# Motor_board_2020_edit.net
KiCad netlist of a schematic drawn in EAGLE
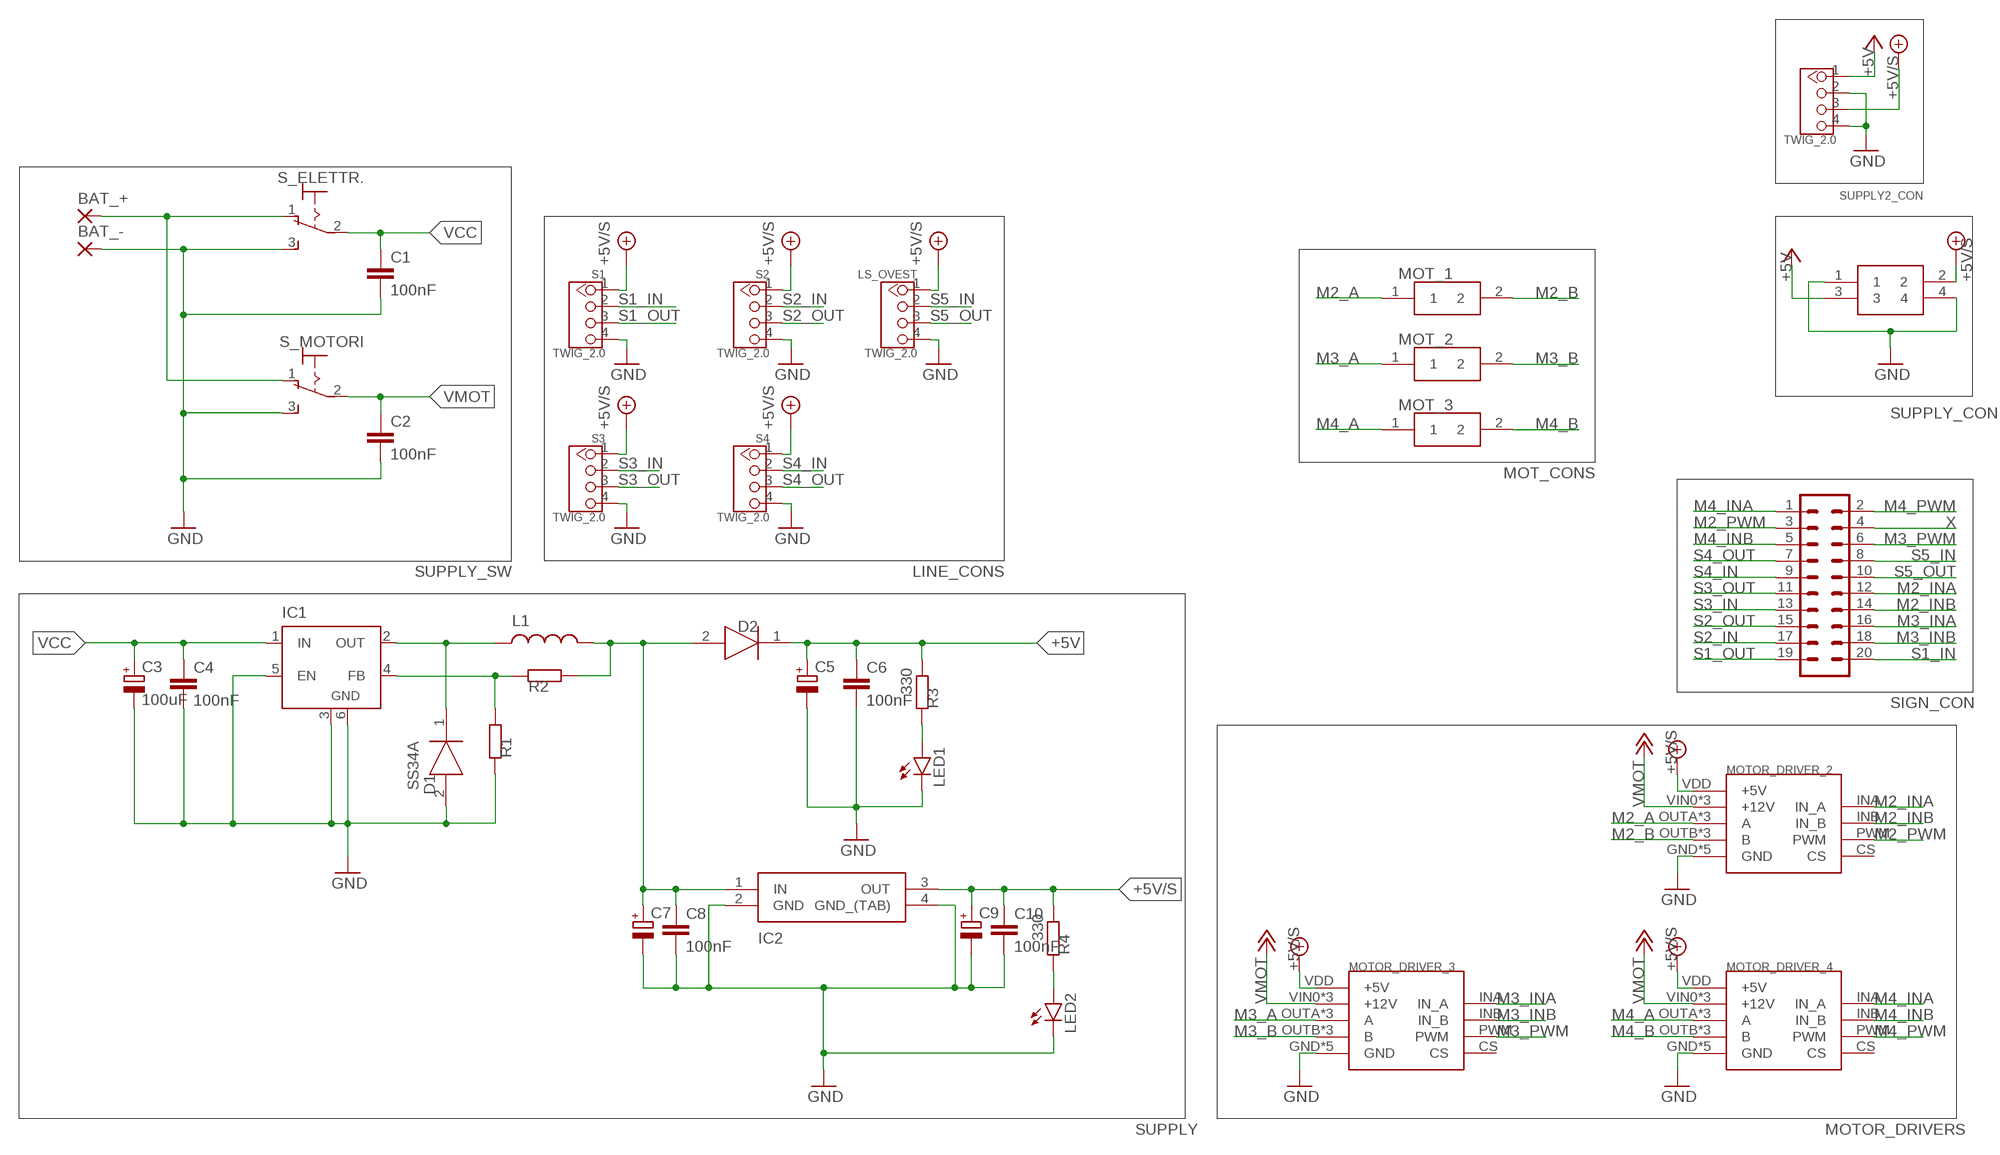
[diagram p0: schematic, sheet 1]

(export (version "E")
  (design (tool "Eeschema 10.0.6"))
  (components
    (comp (ref "BAT_+")
      (value "3,81/1,4")
      (footprint "eagle-import:3,81_1,4")
      (libsource (lib "eagle-import") (part "3,81/1,4"))
    )
    (comp (ref "BAT_-")
      (value "3,81/1,4")
      (footprint "eagle-import:3,81_1,4")
      (libsource (lib "eagle-import") (part "3,81/1,4"))
    )
    (comp (ref "C1")
      (value "100nF")
      (footprint "eagle-import:C1206")
      (libsource (lib "eagle-import") (part "C-EUC1206"))
    )
    (comp (ref "C2")
      (value "100nF")
      (footprint "eagle-import:C1206")
      (libsource (lib "eagle-import") (part "C-EUC1206"))
    )
    (comp (ref "C3")
      (value "100uF")
      (footprint "eagle-import:CT7343")
      (libsource (lib "eagle-import") (part "CPOL-EUCT7343"))
    )
    (comp (ref "C4")
      (value "100nF")
      (footprint "eagle-import:C1206")
      (libsource (lib "eagle-import") (part "C-EUC1206"))
    )
    (comp (ref "C5")
      (value "CPOL-EUE")
      (footprint "eagle-import:PANASONIC_E")
      (libsource (lib "eagle-import") (part "CPOL-EUE"))
    )
    (comp (ref "C6")
      (value "100nF")
      (footprint "eagle-import:C1206")
      (libsource (lib "eagle-import") (part "C-EUC1206"))
    )
    (comp (ref "C7")
      (value "CPOL-EUE")
      (footprint "eagle-import:PANASONIC_E")
      (libsource (lib "eagle-import") (part "CPOL-EUE"))
    )
    (comp (ref "C8")
      (value "100nF")
      (footprint "eagle-import:C1206")
      (libsource (lib "eagle-import") (part "C-EUC1206"))
    )
    (comp (ref "C9")
      (value "CPOL-EUE")
      (footprint "eagle-import:PANASONIC_E")
      (libsource (lib "eagle-import") (part "CPOL-EUE"))
    )
    (comp (ref "C10")
      (value "100nF")
      (footprint "eagle-import:C1206")
      (libsource (lib "eagle-import") (part "C-EUC1206"))
    )
    (comp (ref "D1")
      (value "SS34A")
      (footprint "eagle-import:DIOM5026X262N")
      (fields (field (name "RS_PART_NUMBER") "1711454"))
      (libsource (lib "eagle-import") (part "SS34A"))
    )
    (comp (ref "D2")
      (value "SE20FG-M3_H")
      (footprint "eagle-import:SODFL3718X108N")
      (fields
        (field (name "MANUFACTURER_PART_NUMBER") "SE20FG-M3/H")
        (field (name "RS_PART_NUMBER") "8949262P")
      )
      (libsource (lib "eagle-import") (part "SE20FG-M3_H"))
    )
    (comp (ref "IC1")
      (value "LM2596S")
      (footprint "eagle-import:TO263-5")
      (libsource (lib "eagle-import") (part "LM2596S"))
    )
    (comp (ref "IC2")
      (value "LM2940CS-5.0_NOPB")
      (footprint "eagle-import:TO254P1435X464-4N")
      (fields
        (field (name "MANUFACTURER_PART_NUMBER") "LM2940CS-5.0/NOPB")
        (field (name "MOUSER_PART_NUMBER") "926-LM2940CS-5.0NOPB")
        (field (name "RS_PART_NUMBER") "2508123693")
      )
      (libsource (lib "eagle-import") (part "LM2940CS-5.0_NOPB"))
    )
    (comp (ref "L1")
      (value "47uH")
      (footprint "eagle-import:MSS1260")
      (libsource (lib "eagle-import") (part "MSS1260"))
    )
    (comp (ref "LED1")
      (value "LEDSML1206")
      (footprint "eagle-import:SML1206")
      (libsource (lib "eagle-import") (part "LEDSML1206"))
    )
    (comp (ref "LED2")
      (value "LEDSML1206")
      (footprint "eagle-import:SML1206")
      (libsource (lib "eagle-import") (part "LEDSML1206"))
    )
    (comp (ref "LS_OVEST")
      (value "TWIG_2.0")
      (footprint "eagle-import:2.0_1X4")
      (libsource (lib "eagle-import") (part "TWIG_2.0"))
    )
    (comp (ref "MOTOR_DRIVER_2")
      (value "VNH5019")
      (footprint "eagle-import:VNH5019")
      (libsource (lib "eagle-import") (part "VNH5019"))
    )
    (comp (ref "MOTOR_DRIVER_3")
      (value "VNH5019")
      (footprint "eagle-import:VNH5019")
      (libsource (lib "eagle-import") (part "VNH5019"))
    )
    (comp (ref "MOTOR_DRIVER_4")
      (value "VNH5019")
      (footprint "eagle-import:VNH5019")
      (libsource (lib "eagle-import") (part "VNH5019"))
    )
    (comp (ref "MOT_1")
      (value "43650-0201")
      (footprint "eagle-import:43650-0200")
      (fields (field (name "MOUSER_PART_NUMBER") "538-43650-0201"))
      (libsource (lib "eagle-import") (part "43650-0201"))
    )
    (comp (ref "MOT_2")
      (value "43650-0201")
      (footprint "eagle-import:43650-0200")
      (fields (field (name "MOUSER_PART_NUMBER") "538-43650-0201"))
      (libsource (lib "eagle-import") (part "43650-0201"))
    )
    (comp (ref "MOT_3")
      (value "43650-0201")
      (footprint "eagle-import:43650-0200")
      (fields (field (name "MOUSER_PART_NUMBER") "538-43650-0201"))
      (libsource (lib "eagle-import") (part "43650-0201"))
    )
    (comp (ref "R1")
      (value "330")
      (footprint "eagle-import:R1206")
      (libsource (lib "eagle-import") (part "R-EU_R1206"))
    )
    (comp (ref "R2")
      (value "1,2k")
      (footprint "eagle-import:R1206")
      (libsource (lib "eagle-import") (part "R-EU_R1206"))
    )
    (comp (ref "R3")
      (value "330")
      (footprint "eagle-import:R1206")
      (libsource (lib "eagle-import") (part "R-EU_R1206"))
    )
    (comp (ref "R4")
      (value "330")
      (footprint "eagle-import:R1206")
      (libsource (lib "eagle-import") (part "R-EU_R1206"))
    )
    (comp (ref "S1")
      (value "TWIG_2.0")
      (footprint "eagle-import:2.0_1X4")
      (libsource (lib "eagle-import") (part "TWIG_2.0"))
    )
    (comp (ref "S2")
      (value "TWIG_2.0")
      (footprint "eagle-import:2.0_1X4")
      (libsource (lib "eagle-import") (part "TWIG_2.0"))
    )
    (comp (ref "S3")
      (value "TWIG_2.0")
      (footprint "eagle-import:2.0_1X4")
      (libsource (lib "eagle-import") (part "TWIG_2.0"))
    )
    (comp (ref "S4")
      (value "TWIG_2.0")
      (footprint "eagle-import:2.0_1X4")
      (libsource (lib "eagle-import") (part "TWIG_2.0"))
    )
    (comp (ref "SIGN_CON")
      (value "20V")
      (footprint "eagle-import:20V")
      (libsource (lib "eagle-import") (part "20V"))
    )
    (comp (ref "SUPPLY2_CON")
      (value "TWIG_2.0")
      (footprint "eagle-import:2.0_1X4")
      (libsource (lib "eagle-import") (part "TWIG_2.0"))
    )
    (comp (ref "SUPPLY_CON")
      (value "39-28-1043")
      (footprint "eagle-import:39-28-1043")
      (fields (field (name "MOUSER_PART_NUMBER") "538-39-28-1043") (field (name "RS_PART_NUMBER") "4841899P"))
      (libsource (lib "eagle-import") (part "39-28-1043"))
    )
    (comp (ref "S_ELETTR.")
      (value "320-916")
      (footprint "eagle-import:320-916")
      (libsource (lib "eagle-import") (part "320-916"))
    )
    (comp (ref "S_MOTORI")
      (value "320-916")
      (footprint "eagle-import:320-916")
      (libsource (lib "eagle-import") (part "320-916"))
    )
  )
  (nets
    (net (code "1") (name "+5V") (class "Default")
      (node (ref "C5") (pin "+") (pinfunction "+_+") (pintype "passive"))
      (node (ref "C6") (pin "1") (pinfunction "1_1") (pintype "passive"))
      (node (ref "D2") (pin "1") (pinfunction "K_1") (pintype "bidirectional"))
      (node (ref "R3") (pin "1") (pinfunction "1_1") (pintype "passive"))
      (node (ref "SUPPLY2_CON") (pin "1") (pinfunction "1_1") (pintype "bidirectional"))
      (node (ref "SUPPLY_CON") (pin "3") (pinfunction "3_3") (pintype "bidirectional"))
    )
    (net (code "2") (name "+5V{slash}S") (class "Default")
      (node (ref "C10") (pin "1") (pinfunction "1_1") (pintype "passive"))
      (node (ref "C9") (pin "+") (pinfunction "+_+") (pintype "passive"))
      (node (ref "IC2") (pin "3") (pinfunction "OUT_3") (pintype "output"))
      (node (ref "LS_OVEST") (pin "1") (pinfunction "1_1") (pintype "bidirectional"))
      (node (ref "MOTOR_DRIVER_2") (pin "VDD") (pinfunction "+5V_VDD") (pintype "bidirectional"))
      (node (ref "MOTOR_DRIVER_3") (pin "VDD") (pinfunction "+5V_VDD") (pintype "bidirectional"))
      (node (ref "MOTOR_DRIVER_4") (pin "VDD") (pinfunction "+5V_VDD") (pintype "bidirectional"))
      (node (ref "R4") (pin "1") (pinfunction "1_1") (pintype "passive"))
      (node (ref "S1") (pin "1") (pinfunction "1_1") (pintype "bidirectional"))
      (node (ref "S2") (pin "1") (pinfunction "1_1") (pintype "bidirectional"))
      (node (ref "S3") (pin "1") (pinfunction "1_1") (pintype "bidirectional"))
      (node (ref "S4") (pin "1") (pinfunction "1_1") (pintype "bidirectional"))
      (node (ref "SUPPLY2_CON") (pin "3") (pinfunction "3_3") (pintype "bidirectional"))
      (node (ref "SUPPLY_CON") (pin "2") (pinfunction "2_2") (pintype "bidirectional"))
    )
    (net (code "3") (name "/M2_A") (class "Default")
      (node (ref "MOTOR_DRIVER_2") (pin "OUTA") (pinfunction "A_OUTA") (pintype "bidirectional"))
      (node (ref "MOTOR_DRIVER_2") (pin "OUTA2") (pinfunction "A_OUTA2") (pintype "bidirectional"))
      (node (ref "MOTOR_DRIVER_2") (pin "OUTA3") (pinfunction "A_OUTA3") (pintype "bidirectional"))
      (node (ref "MOT_1") (pin "1") (pinfunction "1_1") (pintype "bidirectional"))
    )
    (net (code "4") (name "/M2_B") (class "Default")
      (node (ref "MOTOR_DRIVER_2") (pin "OUTB") (pinfunction "B_OUTB") (pintype "bidirectional"))
      (node (ref "MOTOR_DRIVER_2") (pin "OUTB1") (pinfunction "B_OUTB1") (pintype "bidirectional"))
      (node (ref "MOTOR_DRIVER_2") (pin "OUTB3") (pinfunction "B_OUTB3") (pintype "bidirectional"))
      (node (ref "MOT_1") (pin "2") (pinfunction "2_2") (pintype "bidirectional"))
    )
    (net (code "5") (name "/M2_INA") (class "Default")
      (node (ref "MOTOR_DRIVER_2") (pin "INA") (pinfunction "IN_A_INA") (pintype "bidirectional"))
      (node (ref "SIGN_CON") (pin "12") (pinfunction "12_12") (pintype "passive"))
    )
    (net (code "6") (name "/M2_INB") (class "Default")
      (node (ref "MOTOR_DRIVER_2") (pin "INB") (pinfunction "IN_B_INB") (pintype "bidirectional"))
      (node (ref "SIGN_CON") (pin "14") (pinfunction "14_14") (pintype "passive"))
    )
    (net (code "7") (name "/M2_PWM") (class "Default")
      (node (ref "MOTOR_DRIVER_2") (pin "PWM") (pinfunction "PWM_PWM") (pintype "bidirectional"))
      (node (ref "SIGN_CON") (pin "3") (pinfunction "3_3") (pintype "passive"))
    )
    (net (code "8") (name "/M3_A") (class "Default")
      (node (ref "MOTOR_DRIVER_3") (pin "OUTA") (pinfunction "A_OUTA") (pintype "bidirectional"))
      (node (ref "MOTOR_DRIVER_3") (pin "OUTA2") (pinfunction "A_OUTA2") (pintype "bidirectional"))
      (node (ref "MOTOR_DRIVER_3") (pin "OUTA3") (pinfunction "A_OUTA3") (pintype "bidirectional"))
      (node (ref "MOT_2") (pin "1") (pinfunction "1_1") (pintype "bidirectional"))
    )
    (net (code "9") (name "/M3_B") (class "Default")
      (node (ref "MOTOR_DRIVER_3") (pin "OUTB") (pinfunction "B_OUTB") (pintype "bidirectional"))
      (node (ref "MOTOR_DRIVER_3") (pin "OUTB1") (pinfunction "B_OUTB1") (pintype "bidirectional"))
      (node (ref "MOTOR_DRIVER_3") (pin "OUTB3") (pinfunction "B_OUTB3") (pintype "bidirectional"))
      (node (ref "MOT_2") (pin "2") (pinfunction "2_2") (pintype "bidirectional"))
    )
    (net (code "10") (name "/M3_INA") (class "Default")
      (node (ref "MOTOR_DRIVER_3") (pin "INA") (pinfunction "IN_A_INA") (pintype "bidirectional"))
      (node (ref "SIGN_CON") (pin "16") (pinfunction "16_16") (pintype "passive"))
    )
    (net (code "11") (name "/M3_INB") (class "Default")
      (node (ref "MOTOR_DRIVER_3") (pin "INB") (pinfunction "IN_B_INB") (pintype "bidirectional"))
      (node (ref "SIGN_CON") (pin "18") (pinfunction "18_18") (pintype "passive"))
    )
    (net (code "12") (name "/M3_PWM") (class "Default")
      (node (ref "MOTOR_DRIVER_3") (pin "PWM") (pinfunction "PWM_PWM") (pintype "bidirectional"))
      (node (ref "SIGN_CON") (pin "6") (pinfunction "6_6") (pintype "passive"))
    )
    (net (code "13") (name "/M4_A") (class "Default")
      (node (ref "MOTOR_DRIVER_4") (pin "OUTA") (pinfunction "A_OUTA") (pintype "bidirectional"))
      (node (ref "MOTOR_DRIVER_4") (pin "OUTA2") (pinfunction "A_OUTA2") (pintype "bidirectional"))
      (node (ref "MOTOR_DRIVER_4") (pin "OUTA3") (pinfunction "A_OUTA3") (pintype "bidirectional"))
      (node (ref "MOT_3") (pin "1") (pinfunction "1_1") (pintype "bidirectional"))
    )
    (net (code "14") (name "/M4_B") (class "Default")
      (node (ref "MOTOR_DRIVER_4") (pin "OUTB") (pinfunction "B_OUTB") (pintype "bidirectional"))
      (node (ref "MOTOR_DRIVER_4") (pin "OUTB1") (pinfunction "B_OUTB1") (pintype "bidirectional"))
      (node (ref "MOTOR_DRIVER_4") (pin "OUTB3") (pinfunction "B_OUTB3") (pintype "bidirectional"))
      (node (ref "MOT_3") (pin "2") (pinfunction "2_2") (pintype "bidirectional"))
    )
    (net (code "15") (name "/M4_INA") (class "Default")
      (node (ref "MOTOR_DRIVER_4") (pin "INA") (pinfunction "IN_A_INA") (pintype "bidirectional"))
      (node (ref "SIGN_CON") (pin "1") (pinfunction "1_1") (pintype "passive"))
    )
    (net (code "16") (name "/M4_INB") (class "Default")
      (node (ref "MOTOR_DRIVER_4") (pin "INB") (pinfunction "IN_B_INB") (pintype "bidirectional"))
      (node (ref "SIGN_CON") (pin "5") (pinfunction "5_5") (pintype "passive"))
    )
    (net (code "17") (name "/M4_PWM") (class "Default")
      (node (ref "MOTOR_DRIVER_4") (pin "PWM") (pinfunction "PWM_PWM") (pintype "bidirectional"))
      (node (ref "SIGN_CON") (pin "2") (pinfunction "2_2") (pintype "passive"))
    )
    (net (code "18") (name "/S1_IN") (class "Default")
      (node (ref "S1") (pin "2") (pinfunction "2_2") (pintype "bidirectional"))
      (node (ref "SIGN_CON") (pin "20") (pinfunction "20_20") (pintype "passive"))
    )
    (net (code "19") (name "/S1_OUT") (class "Default")
      (node (ref "S1") (pin "3") (pinfunction "3_3") (pintype "bidirectional"))
      (node (ref "SIGN_CON") (pin "19") (pinfunction "19_19") (pintype "passive"))
    )
    (net (code "20") (name "/S2_IN") (class "Default")
      (node (ref "S2") (pin "2") (pinfunction "2_2") (pintype "bidirectional"))
      (node (ref "SIGN_CON") (pin "17") (pinfunction "17_17") (pintype "passive"))
    )
    (net (code "21") (name "/S2_OUT") (class "Default")
      (node (ref "S2") (pin "3") (pinfunction "3_3") (pintype "bidirectional"))
      (node (ref "SIGN_CON") (pin "15") (pinfunction "15_15") (pintype "passive"))
    )
    (net (code "22") (name "/S3_IN") (class "Default")
      (node (ref "S3") (pin "2") (pinfunction "2_2") (pintype "bidirectional"))
      (node (ref "SIGN_CON") (pin "13") (pinfunction "13_13") (pintype "passive"))
    )
    (net (code "23") (name "/S3_OUT") (class "Default")
      (node (ref "S3") (pin "3") (pinfunction "3_3") (pintype "bidirectional"))
      (node (ref "SIGN_CON") (pin "11") (pinfunction "11_11") (pintype "passive"))
    )
    (net (code "24") (name "/S4_IN") (class "Default")
      (node (ref "S4") (pin "2") (pinfunction "2_2") (pintype "bidirectional"))
      (node (ref "SIGN_CON") (pin "9") (pinfunction "9_9") (pintype "passive"))
    )
    (net (code "25") (name "/S4_OUT") (class "Default")
      (node (ref "S4") (pin "3") (pinfunction "3_3") (pintype "bidirectional"))
      (node (ref "SIGN_CON") (pin "7") (pinfunction "7_7") (pintype "passive"))
    )
    (net (code "26") (name "/S5_IN") (class "Default")
      (node (ref "LS_OVEST") (pin "2") (pinfunction "2_2") (pintype "bidirectional"))
      (node (ref "SIGN_CON") (pin "8") (pinfunction "8_8") (pintype "passive"))
    )
    (net (code "27") (name "/S5_OUT") (class "Default")
      (node (ref "LS_OVEST") (pin "3") (pinfunction "3_3") (pintype "bidirectional"))
      (node (ref "SIGN_CON") (pin "10") (pinfunction "10_10") (pintype "passive"))
    )
    (net (code "28") (name "/X") (class "Default")
      (node (ref "SIGN_CON") (pin "4") (pinfunction "4_4") (pintype "passive"))
    )
    (net (code "29") (name "GND") (class "Default")
      (node (ref "BAT_-") (pin "1") (pinfunction "P_1") (pintype "passive"))
      (node (ref "C1") (pin "2") (pinfunction "2_2") (pintype "passive"))
      (node (ref "C10") (pin "2") (pinfunction "2_2") (pintype "passive"))
      (node (ref "C2") (pin "2") (pinfunction "2_2") (pintype "passive"))
      (node (ref "C3") (pin "-") (pinfunction "-_-") (pintype "passive"))
      (node (ref "C4") (pin "2") (pinfunction "2_2") (pintype "passive"))
      (node (ref "C5") (pin "-") (pinfunction "-_-") (pintype "passive"))
      (node (ref "C6") (pin "2") (pinfunction "2_2") (pintype "passive"))
      (node (ref "C7") (pin "-") (pinfunction "-_-") (pintype "passive"))
      (node (ref "C8") (pin "2") (pinfunction "2_2") (pintype "passive"))
      (node (ref "C9") (pin "-") (pinfunction "-_-") (pintype "passive"))
      (node (ref "D1") (pin "2") (pinfunction "A_2") (pintype "bidirectional"))
      (node (ref "IC1") (pin "3") (pinfunction "GND_3") (pintype "power_in"))
      (node (ref "IC1") (pin "5") (pinfunction "EN_5") (pintype "input"))
      (node (ref "IC1") (pin "6") (pinfunction "GND_6") (pintype "power_in"))
      (node (ref "IC2") (pin "2") (pinfunction "GND_2") (pintype "power_in"))
      (node (ref "IC2") (pin "4") (pinfunction "GND_(TAB)_4") (pintype "power_in"))
      (node (ref "LED1") (pin "C") (pinfunction "C_C") (pintype "passive"))
      (node (ref "LED2") (pin "C") (pinfunction "C_C") (pintype "passive"))
      (node (ref "LS_OVEST") (pin "4") (pinfunction "4_4") (pintype "bidirectional"))
      (node (ref "MOTOR_DRIVER_2") (pin "GND") (pinfunction "GND_GND") (pintype "bidirectional"))
      (node (ref "MOTOR_DRIVER_2") (pin "GND0") (pinfunction "GND_GND0") (pintype "bidirectional"))
      (node (ref "MOTOR_DRIVER_2") (pin "GND1") (pinfunction "GND_GND1") (pintype "bidirectional"))
      (node (ref "MOTOR_DRIVER_2") (pin "GND2") (pinfunction "GND_GND2") (pintype "bidirectional"))
      (node (ref "MOTOR_DRIVER_2") (pin "GND3") (pinfunction "GND_GND3") (pintype "bidirectional"))
      (node (ref "MOTOR_DRIVER_3") (pin "GND") (pinfunction "GND_GND") (pintype "bidirectional"))
      (node (ref "MOTOR_DRIVER_3") (pin "GND0") (pinfunction "GND_GND0") (pintype "bidirectional"))
      (node (ref "MOTOR_DRIVER_3") (pin "GND1") (pinfunction "GND_GND1") (pintype "bidirectional"))
      (node (ref "MOTOR_DRIVER_3") (pin "GND2") (pinfunction "GND_GND2") (pintype "bidirectional"))
      (node (ref "MOTOR_DRIVER_3") (pin "GND3") (pinfunction "GND_GND3") (pintype "bidirectional"))
      (node (ref "MOTOR_DRIVER_4") (pin "GND") (pinfunction "GND_GND") (pintype "bidirectional"))
      (node (ref "MOTOR_DRIVER_4") (pin "GND0") (pinfunction "GND_GND0") (pintype "bidirectional"))
      (node (ref "MOTOR_DRIVER_4") (pin "GND1") (pinfunction "GND_GND1") (pintype "bidirectional"))
      (node (ref "MOTOR_DRIVER_4") (pin "GND2") (pinfunction "GND_GND2") (pintype "bidirectional"))
      (node (ref "MOTOR_DRIVER_4") (pin "GND3") (pinfunction "GND_GND3") (pintype "bidirectional"))
      (node (ref "R1") (pin "1") (pinfunction "1_1") (pintype "passive"))
      (node (ref "S1") (pin "4") (pinfunction "4_4") (pintype "bidirectional"))
      (node (ref "S2") (pin "4") (pinfunction "4_4") (pintype "bidirectional"))
      (node (ref "S3") (pin "4") (pinfunction "4_4") (pintype "bidirectional"))
      (node (ref "S4") (pin "4") (pinfunction "4_4") (pintype "bidirectional"))
      (node (ref "SUPPLY2_CON") (pin "2") (pinfunction "2_2") (pintype "bidirectional"))
      (node (ref "SUPPLY2_CON") (pin "4") (pinfunction "4_4") (pintype "bidirectional"))
      (node (ref "SUPPLY_CON") (pin "1") (pinfunction "1_1") (pintype "bidirectional"))
      (node (ref "SUPPLY_CON") (pin "4") (pinfunction "4_4") (pintype "bidirectional"))
      (node (ref "S_ELETTR.") (pin "3") (pinfunction "S_3") (pintype "passive"))
      (node (ref "S_MOTORI") (pin "3") (pinfunction "S_3") (pintype "passive"))
    )
    (net (code "30") (name "Net-(BAT_+-P)") (class "Default")
      (node (ref "BAT_+") (pin "1") (pinfunction "P_1") (pintype "passive"))
      (node (ref "S_ELETTR.") (pin "1") (pinfunction "O_1") (pintype "passive"))
      (node (ref "S_MOTORI") (pin "1") (pinfunction "O_1") (pintype "passive"))
    )
    (net (code "31") (name "Net-(D1-K)") (class "Default")
      (node (ref "D1") (pin "1") (pinfunction "K_1") (pintype "bidirectional"))
      (node (ref "IC1") (pin "2") (pinfunction "OUT_2") (pintype "output"))
      (node (ref "L1") (pin "P$2") (pinfunction "P$2_P$2") (pintype "passive"))
    )
    (net (code "32") (name "Net-(D2-A)") (class "Default")
      (node (ref "C7") (pin "+") (pinfunction "+_+") (pintype "passive"))
      (node (ref "C8") (pin "1") (pinfunction "1_1") (pintype "passive"))
      (node (ref "D2") (pin "2") (pinfunction "A_2") (pintype "bidirectional"))
      (node (ref "IC2") (pin "1") (pinfunction "IN_1") (pintype "input"))
      (node (ref "L1") (pin "P$1") (pinfunction "P$1_P$1") (pintype "passive"))
      (node (ref "R2") (pin "1") (pinfunction "1_1") (pintype "passive"))
    )
    (net (code "33") (name "Net-(IC1-FB)") (class "Default")
      (node (ref "IC1") (pin "4") (pinfunction "FB_4") (pintype "input"))
      (node (ref "R1") (pin "2") (pinfunction "2_2") (pintype "passive"))
      (node (ref "R2") (pin "2") (pinfunction "2_2") (pintype "passive"))
    )
    (net (code "34") (name "Net-(LED1-PadA)") (class "Default")
      (node (ref "LED1") (pin "A") (pinfunction "A_A") (pintype "passive"))
      (node (ref "R3") (pin "2") (pinfunction "2_2") (pintype "passive"))
    )
    (net (code "35") (name "Net-(LED2-PadA)") (class "Default")
      (node (ref "LED2") (pin "A") (pinfunction "A_A") (pintype "passive"))
      (node (ref "R4") (pin "2") (pinfunction "2_2") (pintype "passive"))
    )
    (net (code "36") (name "VCC") (class "Default")
      (node (ref "C1") (pin "1") (pinfunction "1_1") (pintype "passive"))
      (node (ref "C3") (pin "+") (pinfunction "+_+") (pintype "passive"))
      (node (ref "C4") (pin "1") (pinfunction "1_1") (pintype "passive"))
      (node (ref "IC1") (pin "1") (pinfunction "IN_1") (pintype "input"))
      (node (ref "S_ELETTR.") (pin "2") (pinfunction "P_2") (pintype "passive"))
    )
    (net (code "37") (name "VMOT") (class "Default")
      (node (ref "C2") (pin "1") (pinfunction "1_1") (pintype "passive"))
      (node (ref "MOTOR_DRIVER_2") (pin "VIN0") (pinfunction "+12V_VIN0") (pintype "bidirectional"))
      (node (ref "MOTOR_DRIVER_2") (pin "VIN1") (pinfunction "+12V_VIN1") (pintype "bidirectional"))
      (node (ref "MOTOR_DRIVER_2") (pin "VIN2") (pinfunction "+12V_VIN2") (pintype "bidirectional"))
      (node (ref "MOTOR_DRIVER_3") (pin "VIN0") (pinfunction "+12V_VIN0") (pintype "bidirectional"))
      (node (ref "MOTOR_DRIVER_3") (pin "VIN1") (pinfunction "+12V_VIN1") (pintype "bidirectional"))
      (node (ref "MOTOR_DRIVER_3") (pin "VIN2") (pinfunction "+12V_VIN2") (pintype "bidirectional"))
      (node (ref "MOTOR_DRIVER_4") (pin "VIN0") (pinfunction "+12V_VIN0") (pintype "bidirectional"))
      (node (ref "MOTOR_DRIVER_4") (pin "VIN1") (pinfunction "+12V_VIN1") (pintype "bidirectional"))
      (node (ref "MOTOR_DRIVER_4") (pin "VIN2") (pinfunction "+12V_VIN2") (pintype "bidirectional"))
      (node (ref "S_MOTORI") (pin "2") (pinfunction "P_2") (pintype "passive"))
    )
    (net (code "38") (name "unconnected-(MOTOR_DRIVER_2-PadCS)") (class "Default")
      (node (ref "MOTOR_DRIVER_2") (pin "CS") (pinfunction "CS_CS") (pintype "bidirectional"))
    )
    (net (code "39") (name "unconnected-(MOTOR_DRIVER_3-PadCS)") (class "Default")
      (node (ref "MOTOR_DRIVER_3") (pin "CS") (pinfunction "CS_CS") (pintype "bidirectional"))
    )
    (net (code "40") (name "unconnected-(MOTOR_DRIVER_4-PadCS)") (class "Default")
      (node (ref "MOTOR_DRIVER_4") (pin "CS") (pinfunction "CS_CS") (pintype "bidirectional"))
    )
  )
)
